# ADC_0.net
KiCad netlist of a schematic drawn in Altium Designer
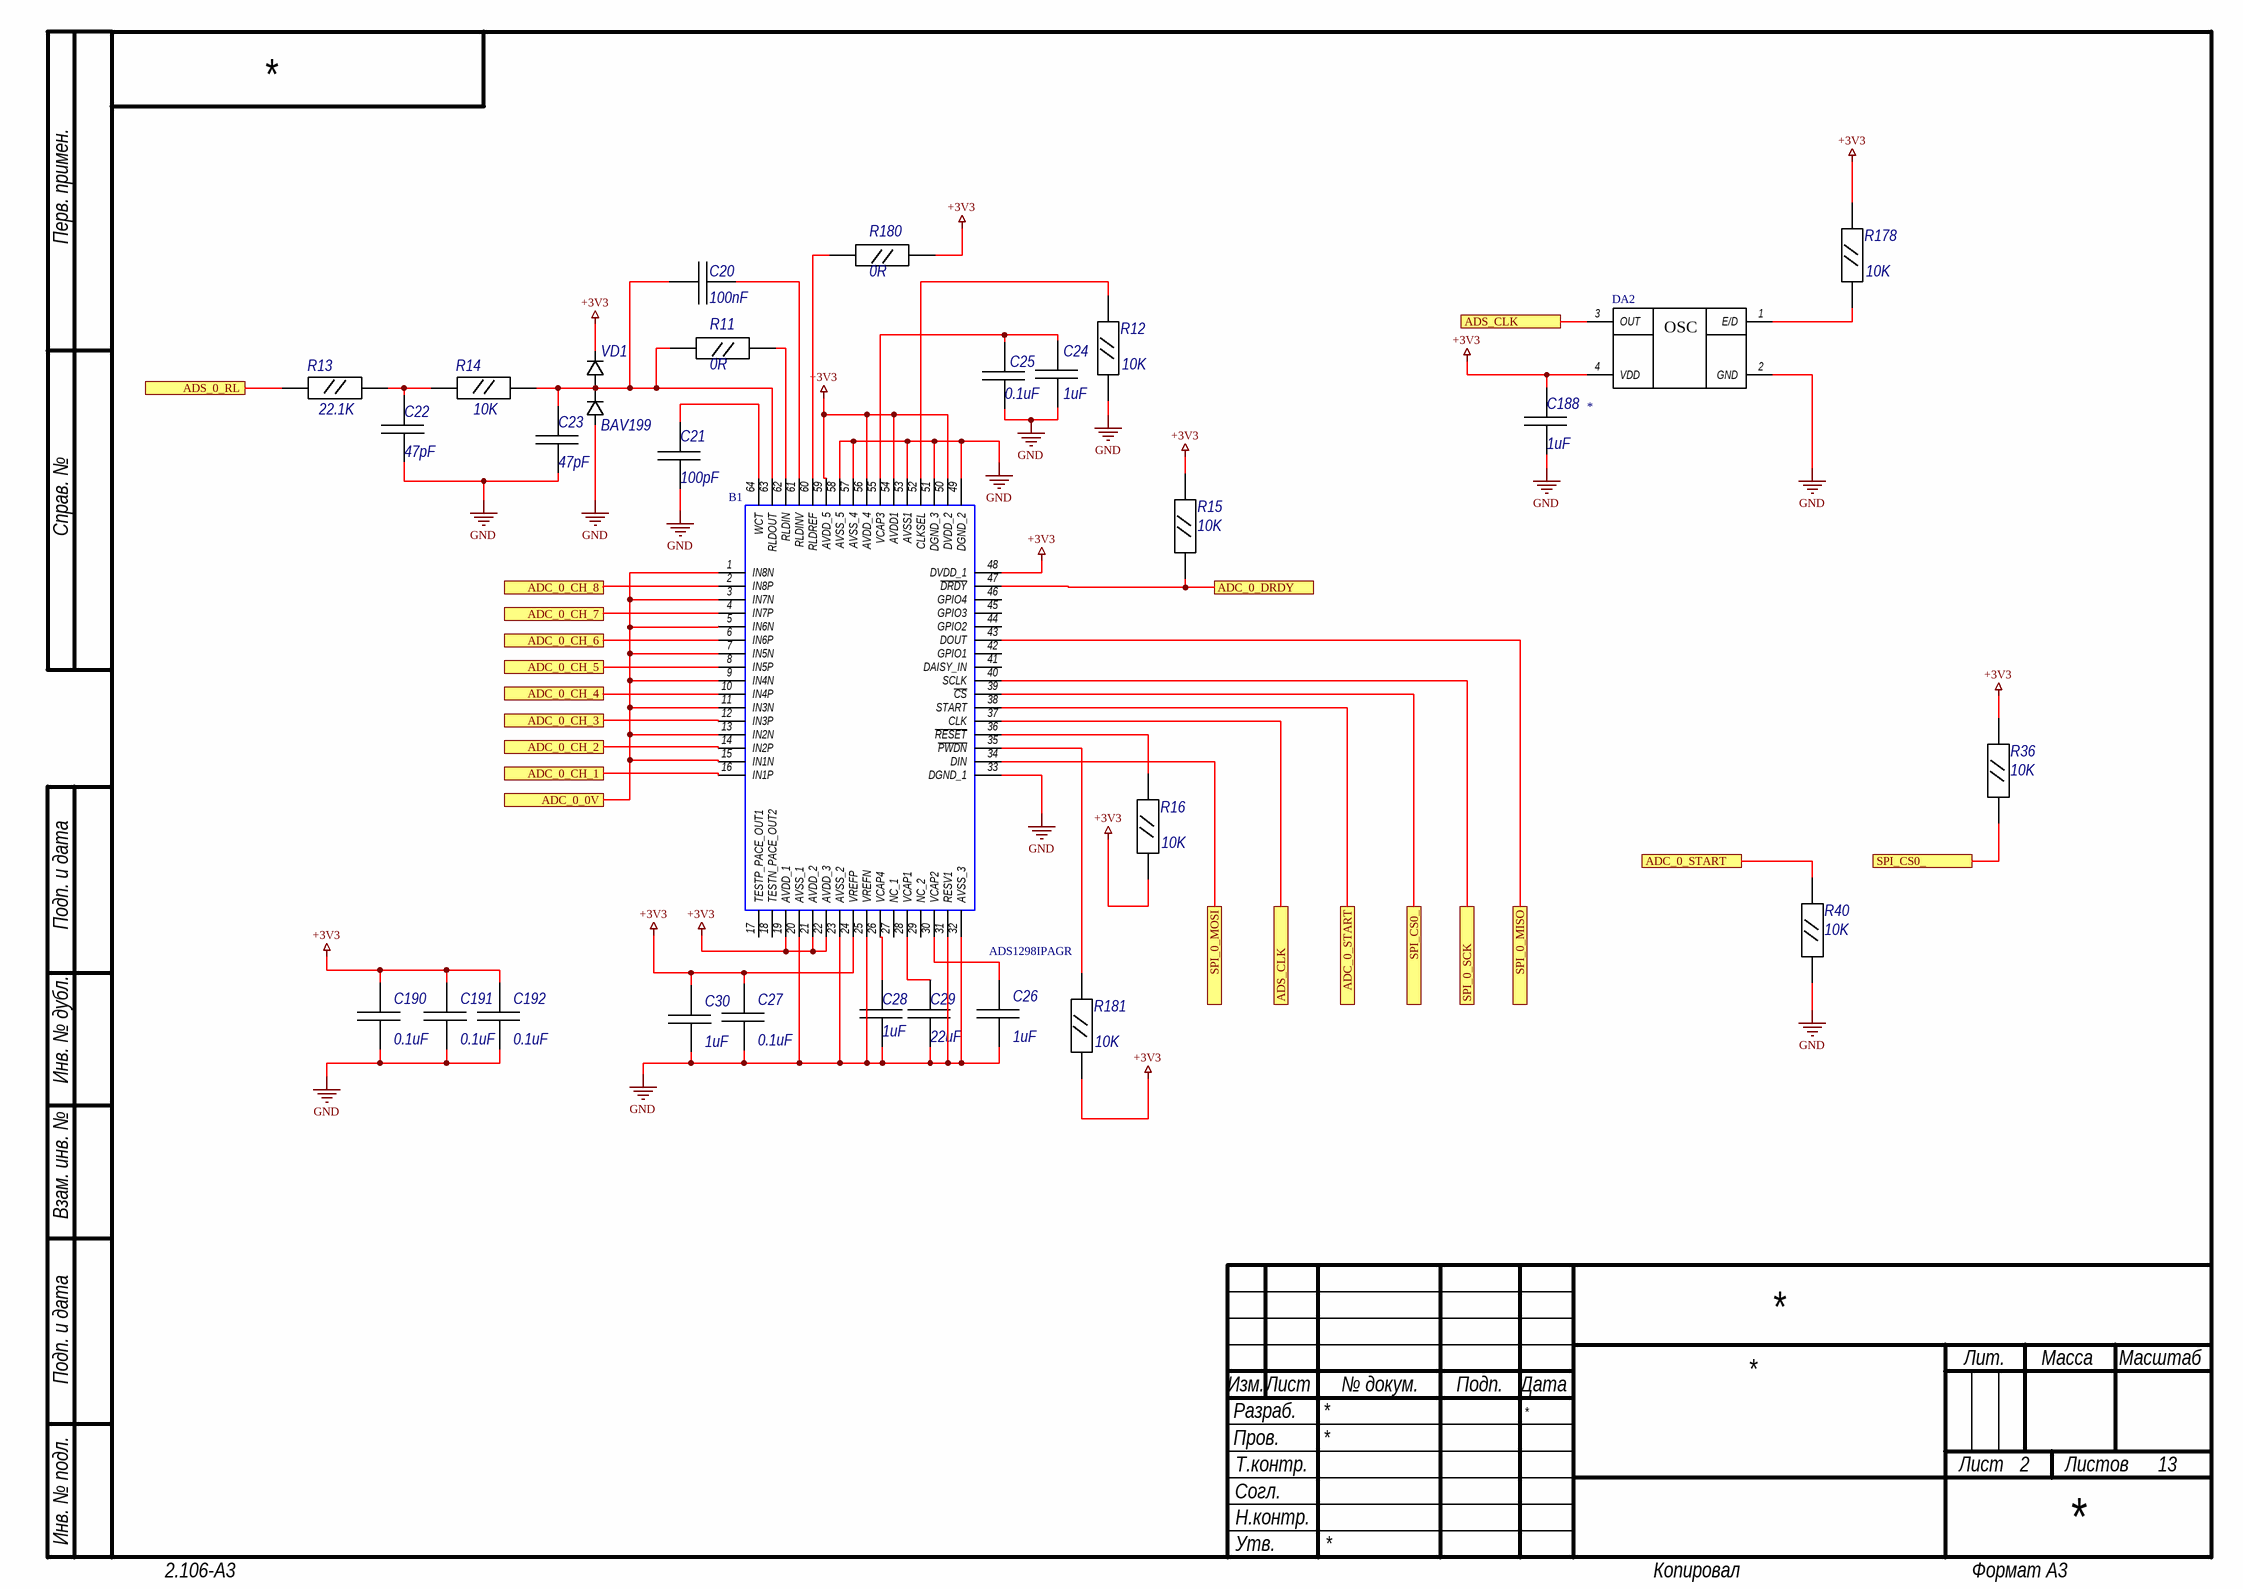
[diagram p0: ADC_0.SchDoc]

(export (version "E")
  (design (tool "Eeschema 10.0.6"))
  (components
    (comp (ref "B1")
      (value "ADS1298IPAGR")
      (footprint "QFP50P1200X1200X120-64N")
      (description "8-Channel 24-bit ADC With Integrated ECG Front End")
      (fields (field (name "MOUSER PART NUMBER") "595-ADS1298IPAGR"))
      (libsource (lib "ADS1298IPAGR") (part "ADS1298IPAGR"))
    )
    (comp (ref "C20")
      (value "100nF")
      (footprint "C0603")
      (description "Ceramic Capacitor SMD")
      (libsource (lib "GOST") (part "CC_SMD_0603"))
    )
    (comp (ref "C21")
      (value "100pF")
      (footprint "C0603")
      (description "Ceramic Capacitor SMD")
      (libsource (lib "GOST") (part "CC_SMD_0603"))
    )
    (comp (ref "C22")
      (value "47pF")
      (footprint "C0603")
      (description "Ceramic Capacitor SMD")
      (libsource (lib "GOST") (part "CC_SMD_0603"))
    )
    (comp (ref "C23")
      (value "47pF")
      (footprint "C0603")
      (description "Ceramic Capacitor SMD")
      (libsource (lib "GOST") (part "CC_SMD_0603"))
    )
    (comp (ref "C24")
      (value "1uF")
      (footprint "C0603")
      (description "Ceramic Capacitor SMD")
      (libsource (lib "GOST") (part "CC_SMD_0603"))
    )
    (comp (ref "C25")
      (value "0.1uF")
      (footprint "C0603")
      (description "Ceramic Capacitor SMD")
      (libsource (lib "GOST") (part "CC_SMD_0603"))
    )
    (comp (ref "C26")
      (value "1uF")
      (footprint "C0603")
      (description "Ceramic Capacitor SMD")
      (libsource (lib "GOST") (part "CC_SMD_0603"))
    )
    (comp (ref "C27")
      (value "0.1uF")
      (footprint "C0603")
      (description "Ceramic Capacitor SMD")
      (libsource (lib "GOST") (part "CC_SMD_0603"))
    )
    (comp (ref "C28")
      (value "1uF")
      (footprint "C0603")
      (description "Ceramic Capacitor SMD")
      (libsource (lib "GOST") (part "CC_SMD_0603"))
    )
    (comp (ref "C29")
      (value "22uF")
      (footprint "C0603")
      (description "Ceramic Capacitor SMD")
      (libsource (lib "GOST") (part "CC_SMD_0603"))
    )
    (comp (ref "C30")
      (value "1uF")
      (footprint "C0603")
      (description "Ceramic Capacitor SMD")
      (libsource (lib "GOST") (part "CC_SMD_0603"))
    )
    (comp (ref "C188")
      (value "1uF")
      (footprint "C0603")
      (description "Ceramic Capacitor SMD")
      (libsource (lib "GOST") (part "CC_SMD_0603"))
    )
    (comp (ref "C190")
      (value "0.1uF")
      (footprint "C0603")
      (description "Ceramic Capacitor SMD")
      (libsource (lib "GOST") (part "CC_SMD_0603"))
    )
    (comp (ref "C191")
      (value "0.1uF")
      (footprint "C0603")
      (description "Ceramic Capacitor SMD")
      (libsource (lib "GOST") (part "CC_SMD_0603"))
    )
    (comp (ref "C192")
      (value "0.1uF")
      (footprint "C0603")
      (description "Ceramic Capacitor SMD")
      (libsource (lib "GOST") (part "CC_SMD_0603"))
    )
    (comp (ref "DA2")
      (value "*")
      (footprint "Quartz 3.2х3.5х0.8")
      (description "Oscillator")
      (libsource (lib "GOST") (part "OSCILLATOR KX-7"))
    )
    (comp (ref "R11")
      (value "0R")
      (footprint "R0603")
      (description "Resistor SMD")
      (libsource (lib "GOST") (part "R0603"))
    )
    (comp (ref "R12")
      (value "10K")
      (footprint "R0603")
      (description "Resistor SMD")
      (libsource (lib "GOST") (part "R0603"))
    )
    (comp (ref "R13")
      (value "22.1K")
      (footprint "R0603")
      (description "Resistor SMD")
      (libsource (lib "") (part "R0603_1"))
    )
    (comp (ref "R14")
      (value "10K")
      (footprint "R0603")
      (description "Resistor SMD")
      (libsource (lib "") (part "R0603_1"))
    )
    (comp (ref "R15")
      (value "10K")
      (footprint "R0603")
      (description "Resistor SMD")
      (libsource (lib "") (part "R0603_1"))
    )
    (comp (ref "R16")
      (value "10K")
      (footprint "R0603")
      (description "Resistor SMD")
      (libsource (lib "GOST") (part "R0603"))
    )
    (comp (ref "R36")
      (value "10K")
      (footprint "R0603")
      (description "Resistor SMD")
      (libsource (lib "") (part "R0603_2"))
    )
    (comp (ref "R40")
      (value "10K")
      (footprint "R0603")
      (description "Resistor SMD")
      (libsource (lib "") (part "R0603_2"))
    )
    (comp (ref "R178")
      (value "10K")
      (footprint "R0603")
      (description "Resistor SMD")
      (libsource (lib "GOST") (part "R0603"))
    )
    (comp (ref "R180")
      (value "0R")
      (footprint "R0603")
      (description "Resistor SMD")
      (libsource (lib "GOST") (part "R0603"))
    )
    (comp (ref "R181")
      (value "10K")
      (footprint "R0603")
      (description "Resistor SMD")
      (libsource (lib "GOST") (part "R0603"))
    )
    (comp (ref "VD1")
      (value "BAV199")
      (footprint "SOT23")
      (description "Diod Schottky")
      (fields (field (name "MANUFACTURER PART NUMBER 1") "BAV199"))
      (libsource (lib "GOST") (part "DIODE_BAV199"))
    )
  )
  (nets
    (net (code "1") (name "+3V3") (class "Default")
      (node (ref "B1") (pin "19") (pinfunction "AVDD_1_19") (pintype "passive"))
      (node (ref "B1") (pin "21") (pinfunction "AVDD_2_21") (pintype "passive"))
      (node (ref "B1") (pin "22") (pinfunction "AVDD_3_22") (pintype "passive"))
      (node (ref "B1") (pin "24") (pinfunction "VREFP_24") (pintype "passive"))
      (node (ref "B1") (pin "48") (pinfunction "DVDD_1_48") (pintype "passive"))
      (node (ref "B1") (pin "50") (pinfunction "DVDD_2_50") (pintype "passive"))
      (node (ref "B1") (pin "54") (pinfunction "AVDD1_54") (pintype "passive"))
      (node (ref "B1") (pin "56") (pinfunction "AVDD_4_56") (pintype "passive"))
      (node (ref "B1") (pin "59") (pinfunction "AVDD_5_59") (pintype "passive"))
      (node (ref "C188") (pin "2") (pinfunction "2_2") (pintype "passive"))
      (node (ref "C190") (pin "2") (pinfunction "2_2") (pintype "passive"))
      (node (ref "C191") (pin "2") (pinfunction "2_2") (pintype "passive"))
      (node (ref "C192") (pin "2") (pinfunction "2_2") (pintype "passive"))
      (node (ref "C27") (pin "2") (pinfunction "2_2") (pintype "passive"))
      (node (ref "C30") (pin "2") (pinfunction "2_2") (pintype "passive"))
      (node (ref "DA2") (pin "4") (pinfunction "VDD_4") (pintype "passive"))
      (node (ref "R15") (pin "2") (pinfunction "2_2") (pintype "passive"))
      (node (ref "R16") (pin "1") (pinfunction "1_1") (pintype "passive"))
      (node (ref "R178") (pin "2") (pinfunction "2_2") (pintype "passive"))
      (node (ref "R180") (pin "1") (pinfunction "1_1") (pintype "passive"))
      (node (ref "R181") (pin "1") (pinfunction "1_1") (pintype "passive"))
      (node (ref "R36") (pin "2") (pinfunction "2_2") (pintype "passive"))
      (node (ref "VD1") (pin "2") (pinfunction "2_2") (pintype "passive"))
    )
    (net (code "2") (name "/ADC_0_0V") (class "Default")
      (node (ref "B1") (pin "1") (pinfunction "IN8N_1") (pintype "passive"))
      (node (ref "B1") (pin "11") (pinfunction "IN3N_11") (pintype "passive"))
      (node (ref "B1") (pin "13") (pinfunction "IN2N_13") (pintype "passive"))
      (node (ref "B1") (pin "15") (pinfunction "IN1N_15") (pintype "passive"))
      (node (ref "B1") (pin "3") (pinfunction "IN7N_3") (pintype "passive"))
      (node (ref "B1") (pin "5") (pinfunction "IN6N_5") (pintype "passive"))
      (node (ref "B1") (pin "7") (pinfunction "IN5N_7") (pintype "passive"))
      (node (ref "B1") (pin "9") (pinfunction "IN4N_9") (pintype "passive"))
    )
    (net (code "3") (name "/ADC_0_CH_1") (class "Default")
      (node (ref "B1") (pin "16") (pinfunction "IN1P_16") (pintype "passive"))
    )
    (net (code "4") (name "/ADC_0_CH_2") (class "Default")
      (node (ref "B1") (pin "14") (pinfunction "IN2P_14") (pintype "passive"))
    )
    (net (code "5") (name "/ADC_0_CH_3") (class "Default")
      (node (ref "B1") (pin "12") (pinfunction "IN3P_12") (pintype "passive"))
    )
    (net (code "6") (name "/ADC_0_CH_4") (class "Default")
      (node (ref "B1") (pin "10") (pinfunction "IN4P_10") (pintype "passive"))
    )
    (net (code "7") (name "/ADC_0_CH_5") (class "Default")
      (node (ref "B1") (pin "8") (pinfunction "IN5P_8") (pintype "passive"))
    )
    (net (code "8") (name "/ADC_0_CH_6") (class "Default")
      (node (ref "B1") (pin "6") (pinfunction "IN6P_6") (pintype "passive"))
    )
    (net (code "9") (name "/ADC_0_CH_7") (class "Default")
      (node (ref "B1") (pin "4") (pinfunction "IN7P_4") (pintype "passive"))
    )
    (net (code "10") (name "/ADC_0_CH_8") (class "Default")
      (node (ref "B1") (pin "2") (pinfunction "IN8P_2") (pintype "passive"))
    )
    (net (code "11") (name "/ADC_0_DRDY") (class "Default")
      (node (ref "B1") (pin "47") (pinfunction "DRDY_47") (pintype "passive"))
      (node (ref "R15") (pin "1") (pinfunction "1_1") (pintype "passive"))
    )
    (net (code "12") (name "/ADC_0_START") (class "Default")
      (node (ref "B1") (pin "38") (pinfunction "START_38") (pintype "passive"))
      (node (ref "R40") (pin "2") (pinfunction "2_2") (pintype "passive"))
    )
    (net (code "13") (name "/ADS_0_RL") (class "Default")
      (node (ref "R13") (pin "1") (pinfunction "1_1") (pintype "passive"))
    )
    (net (code "14") (name "/ADS_CLK") (class "Default")
      (node (ref "B1") (pin "37") (pinfunction "CLK_37") (pintype "passive"))
      (node (ref "DA2") (pin "3") (pinfunction "OUT_3") (pintype "passive"))
    )
    (net (code "15") (name "/SPI_0_MISO") (class "Default")
      (node (ref "B1") (pin "43") (pinfunction "DOUT_43") (pintype "passive"))
    )
    (net (code "16") (name "/SPI_0_MOSI") (class "Default")
      (node (ref "B1") (pin "34") (pinfunction "DIN_34") (pintype "passive"))
    )
    (net (code "17") (name "/SPI_0_SCK") (class "Default")
      (node (ref "B1") (pin "40") (pinfunction "SCLK_40") (pintype "passive"))
    )
    (net (code "18") (name "/SPI_CS0_") (class "Default")
      (node (ref "B1") (pin "39") (pinfunction "CS_39") (pintype "passive"))
      (node (ref "R36") (pin "1") (pinfunction "1_1") (pintype "passive"))
    )
    (net (code "19") (name "GND") (class "Default")
      (node (ref "B1") (pin "20") (pinfunction "AVSS_1_20") (pintype "passive"))
      (node (ref "B1") (pin "23") (pinfunction "AVSS_2_23") (pintype "passive"))
      (node (ref "B1") (pin "25") (pinfunction "VREFN_25") (pintype "passive"))
      (node (ref "B1") (pin "31") (pinfunction "RESV1_31") (pintype "passive"))
      (node (ref "B1") (pin "32") (pinfunction "AVSS_3_32") (pintype "passive"))
      (node (ref "B1") (pin "33") (pinfunction "DGND_1_33") (pintype "passive"))
      (node (ref "B1") (pin "49") (pinfunction "DGND_2_49") (pintype "passive"))
      (node (ref "B1") (pin "51") (pinfunction "DGND_3_51") (pintype "passive"))
      (node (ref "B1") (pin "53") (pinfunction "AVSS1_53") (pintype "passive"))
      (node (ref "B1") (pin "57") (pinfunction "AVSS_4_57") (pintype "passive"))
      (node (ref "B1") (pin "58") (pinfunction "AVSS_5_58") (pintype "passive"))
      (node (ref "C188") (pin "1") (pinfunction "1_1") (pintype "passive"))
      (node (ref "C190") (pin "1") (pinfunction "1_1") (pintype "passive"))
      (node (ref "C191") (pin "1") (pinfunction "1_1") (pintype "passive"))
      (node (ref "C192") (pin "1") (pinfunction "1_1") (pintype "passive"))
      (node (ref "C21") (pin "1") (pinfunction "1_1") (pintype "passive"))
      (node (ref "C22") (pin "1") (pinfunction "1_1") (pintype "passive"))
      (node (ref "C23") (pin "1") (pinfunction "1_1") (pintype "passive"))
      (node (ref "C24") (pin "1") (pinfunction "1_1") (pintype "passive"))
      (node (ref "C25") (pin "1") (pinfunction "1_1") (pintype "passive"))
      (node (ref "C26") (pin "1") (pinfunction "1_1") (pintype "passive"))
      (node (ref "C27") (pin "1") (pinfunction "1_1") (pintype "passive"))
      (node (ref "C28") (pin "1") (pinfunction "1_1") (pintype "passive"))
      (node (ref "C29") (pin "1") (pinfunction "1_1") (pintype "passive"))
      (node (ref "C30") (pin "1") (pinfunction "1_1") (pintype "passive"))
      (node (ref "DA2") (pin "2") (pinfunction "GND_2") (pintype "passive"))
      (node (ref "R12") (pin "1") (pinfunction "1_1") (pintype "passive"))
      (node (ref "R40") (pin "1") (pinfunction "1_1") (pintype "passive"))
      (node (ref "VD1") (pin "1") (pinfunction "1_1") (pintype "passive"))
    )
    (net (code "20") (name "Net-(B1-CLKSEL)") (class "Default")
      (node (ref "B1") (pin "52") (pinfunction "CLKSEL_52") (pintype "passive"))
      (node (ref "R12") (pin "2") (pinfunction "2_2") (pintype "passive"))
    )
    (net (code "21") (name "Net-(B1-PWDN)") (class "Default")
      (node (ref "B1") (pin "35") (pinfunction "PWDN_35") (pintype "passive"))
      (node (ref "R181") (pin "2") (pinfunction "2_2") (pintype "passive"))
    )
    (net (code "22") (name "Net-(B1-RESET)") (class "Default")
      (node (ref "B1") (pin "36") (pinfunction "RESET_36") (pintype "passive"))
      (node (ref "R16") (pin "2") (pinfunction "2_2") (pintype "passive"))
    )
    (net (code "23") (name "Net-(B1-RLDIN)") (class "Default")
      (node (ref "B1") (pin "62") (pinfunction "RLDIN_62") (pintype "passive"))
      (node (ref "R11") (pin "1") (pinfunction "1_1") (pintype "passive"))
    )
    (net (code "24") (name "Net-(B1-RLDINV)") (class "Default")
      (node (ref "B1") (pin "61") (pinfunction "RLDINV_61") (pintype "passive"))
      (node (ref "C20") (pin "1") (pinfunction "1_1") (pintype "passive"))
    )
    (net (code "25") (name "Net-(B1-RLDOUT)") (class "Default")
      (node (ref "B1") (pin "63") (pinfunction "RLDOUT_63") (pintype "passive"))
      (node (ref "C20") (pin "2") (pinfunction "2_2") (pintype "passive"))
      (node (ref "C23") (pin "2") (pinfunction "2_2") (pintype "passive"))
      (node (ref "R11") (pin "2") (pinfunction "2_2") (pintype "passive"))
      (node (ref "R14") (pin "2") (pinfunction "2_2") (pintype "passive"))
      (node (ref "VD1") (pin "3") (pinfunction "3_3") (pintype "passive"))
    )
    (net (code "26") (name "Net-(B1-RLDREF)") (class "Default")
      (node (ref "B1") (pin "60") (pinfunction "RLDREF_60") (pintype "passive"))
      (node (ref "R180") (pin "2") (pinfunction "2_2") (pintype "passive"))
    )
    (net (code "27") (name "Net-(B1-VCAP1)") (class "Default")
      (node (ref "B1") (pin "28") (pinfunction "VCAP1_28") (pintype "passive"))
      (node (ref "C29") (pin "2") (pinfunction "2_2") (pintype "passive"))
    )
    (net (code "28") (name "Net-(B1-VCAP2)") (class "Default")
      (node (ref "B1") (pin "30") (pinfunction "VCAP2_30") (pintype "passive"))
      (node (ref "C26") (pin "2") (pinfunction "2_2") (pintype "passive"))
    )
    (net (code "29") (name "Net-(B1-VCAP3)") (class "Default")
      (node (ref "B1") (pin "55") (pinfunction "VCAP3_55") (pintype "passive"))
      (node (ref "C24") (pin "2") (pinfunction "2_2") (pintype "passive"))
      (node (ref "C25") (pin "2") (pinfunction "2_2") (pintype "passive"))
    )
    (net (code "30") (name "Net-(B1-VCAP4)") (class "Default")
      (node (ref "B1") (pin "26") (pinfunction "VCAP4_26") (pintype "passive"))
      (node (ref "C28") (pin "2") (pinfunction "2_2") (pintype "passive"))
    )
    (net (code "31") (name "Net-(B1-WCT)") (class "Default")
      (node (ref "B1") (pin "64") (pinfunction "WCT_64") (pintype "passive"))
      (node (ref "C21") (pin "2") (pinfunction "2_2") (pintype "passive"))
    )
    (net (code "32") (name "Net-(C22-Pad2)") (class "Default")
      (node (ref "C22") (pin "2") (pinfunction "2_2") (pintype "passive"))
      (node (ref "R13") (pin "2") (pinfunction "2_2") (pintype "passive"))
      (node (ref "R14") (pin "1") (pinfunction "1_1") (pintype "passive"))
    )
    (net (code "33") (name "Net-(DA2-E{slash}D)") (class "Default")
      (node (ref "DA2") (pin "1") (pinfunction "E/D_1") (pintype "passive"))
      (node (ref "R178") (pin "1") (pinfunction "1_1") (pintype "passive"))
    )
    (net (code "34") (name "unconnected-(B1-DAISY_IN-Pad41)") (class "Default")
      (node (ref "B1") (pin "41") (pinfunction "DAISY_IN_41") (pintype "passive"))
    )
    (net (code "35") (name "unconnected-(B1-GPIO1-Pad42)") (class "Default")
      (node (ref "B1") (pin "42") (pinfunction "GPIO1_42") (pintype "passive"))
    )
    (net (code "36") (name "unconnected-(B1-GPIO2-Pad44)") (class "Default")
      (node (ref "B1") (pin "44") (pinfunction "GPIO2_44") (pintype "passive"))
    )
    (net (code "37") (name "unconnected-(B1-GPIO3-Pad45)") (class "Default")
      (node (ref "B1") (pin "45") (pinfunction "GPIO3_45") (pintype "passive"))
    )
    (net (code "38") (name "unconnected-(B1-GPIO4-Pad46)") (class "Default")
      (node (ref "B1") (pin "46") (pinfunction "GPIO4_46") (pintype "passive"))
    )
    (net (code "39") (name "unconnected-(B1-NC_1-Pad27)") (class "Default")
      (node (ref "B1") (pin "27") (pinfunction "NC_1_27") (pintype "passive"))
    )
    (net (code "40") (name "unconnected-(B1-NC_2-Pad29)") (class "Default")
      (node (ref "B1") (pin "29") (pinfunction "NC_2_29") (pintype "passive"))
    )
    (net (code "41") (name "unconnected-(B1-TESTN_PACE_OUT2-Pad18)") (class "Default")
      (node (ref "B1") (pin "18") (pinfunction "TESTN_PACE_OUT2_18") (pintype "passive"))
    )
    (net (code "42") (name "unconnected-(B1-TESTP_PACE_OUT1-Pad17)") (class "Default")
      (node (ref "B1") (pin "17") (pinfunction "TESTP_PACE_OUT1_17") (pintype "passive"))
    )
  )
)
